# DM3390_TopLevel.net
KiCad netlist of a schematic drawn in Altium Designer
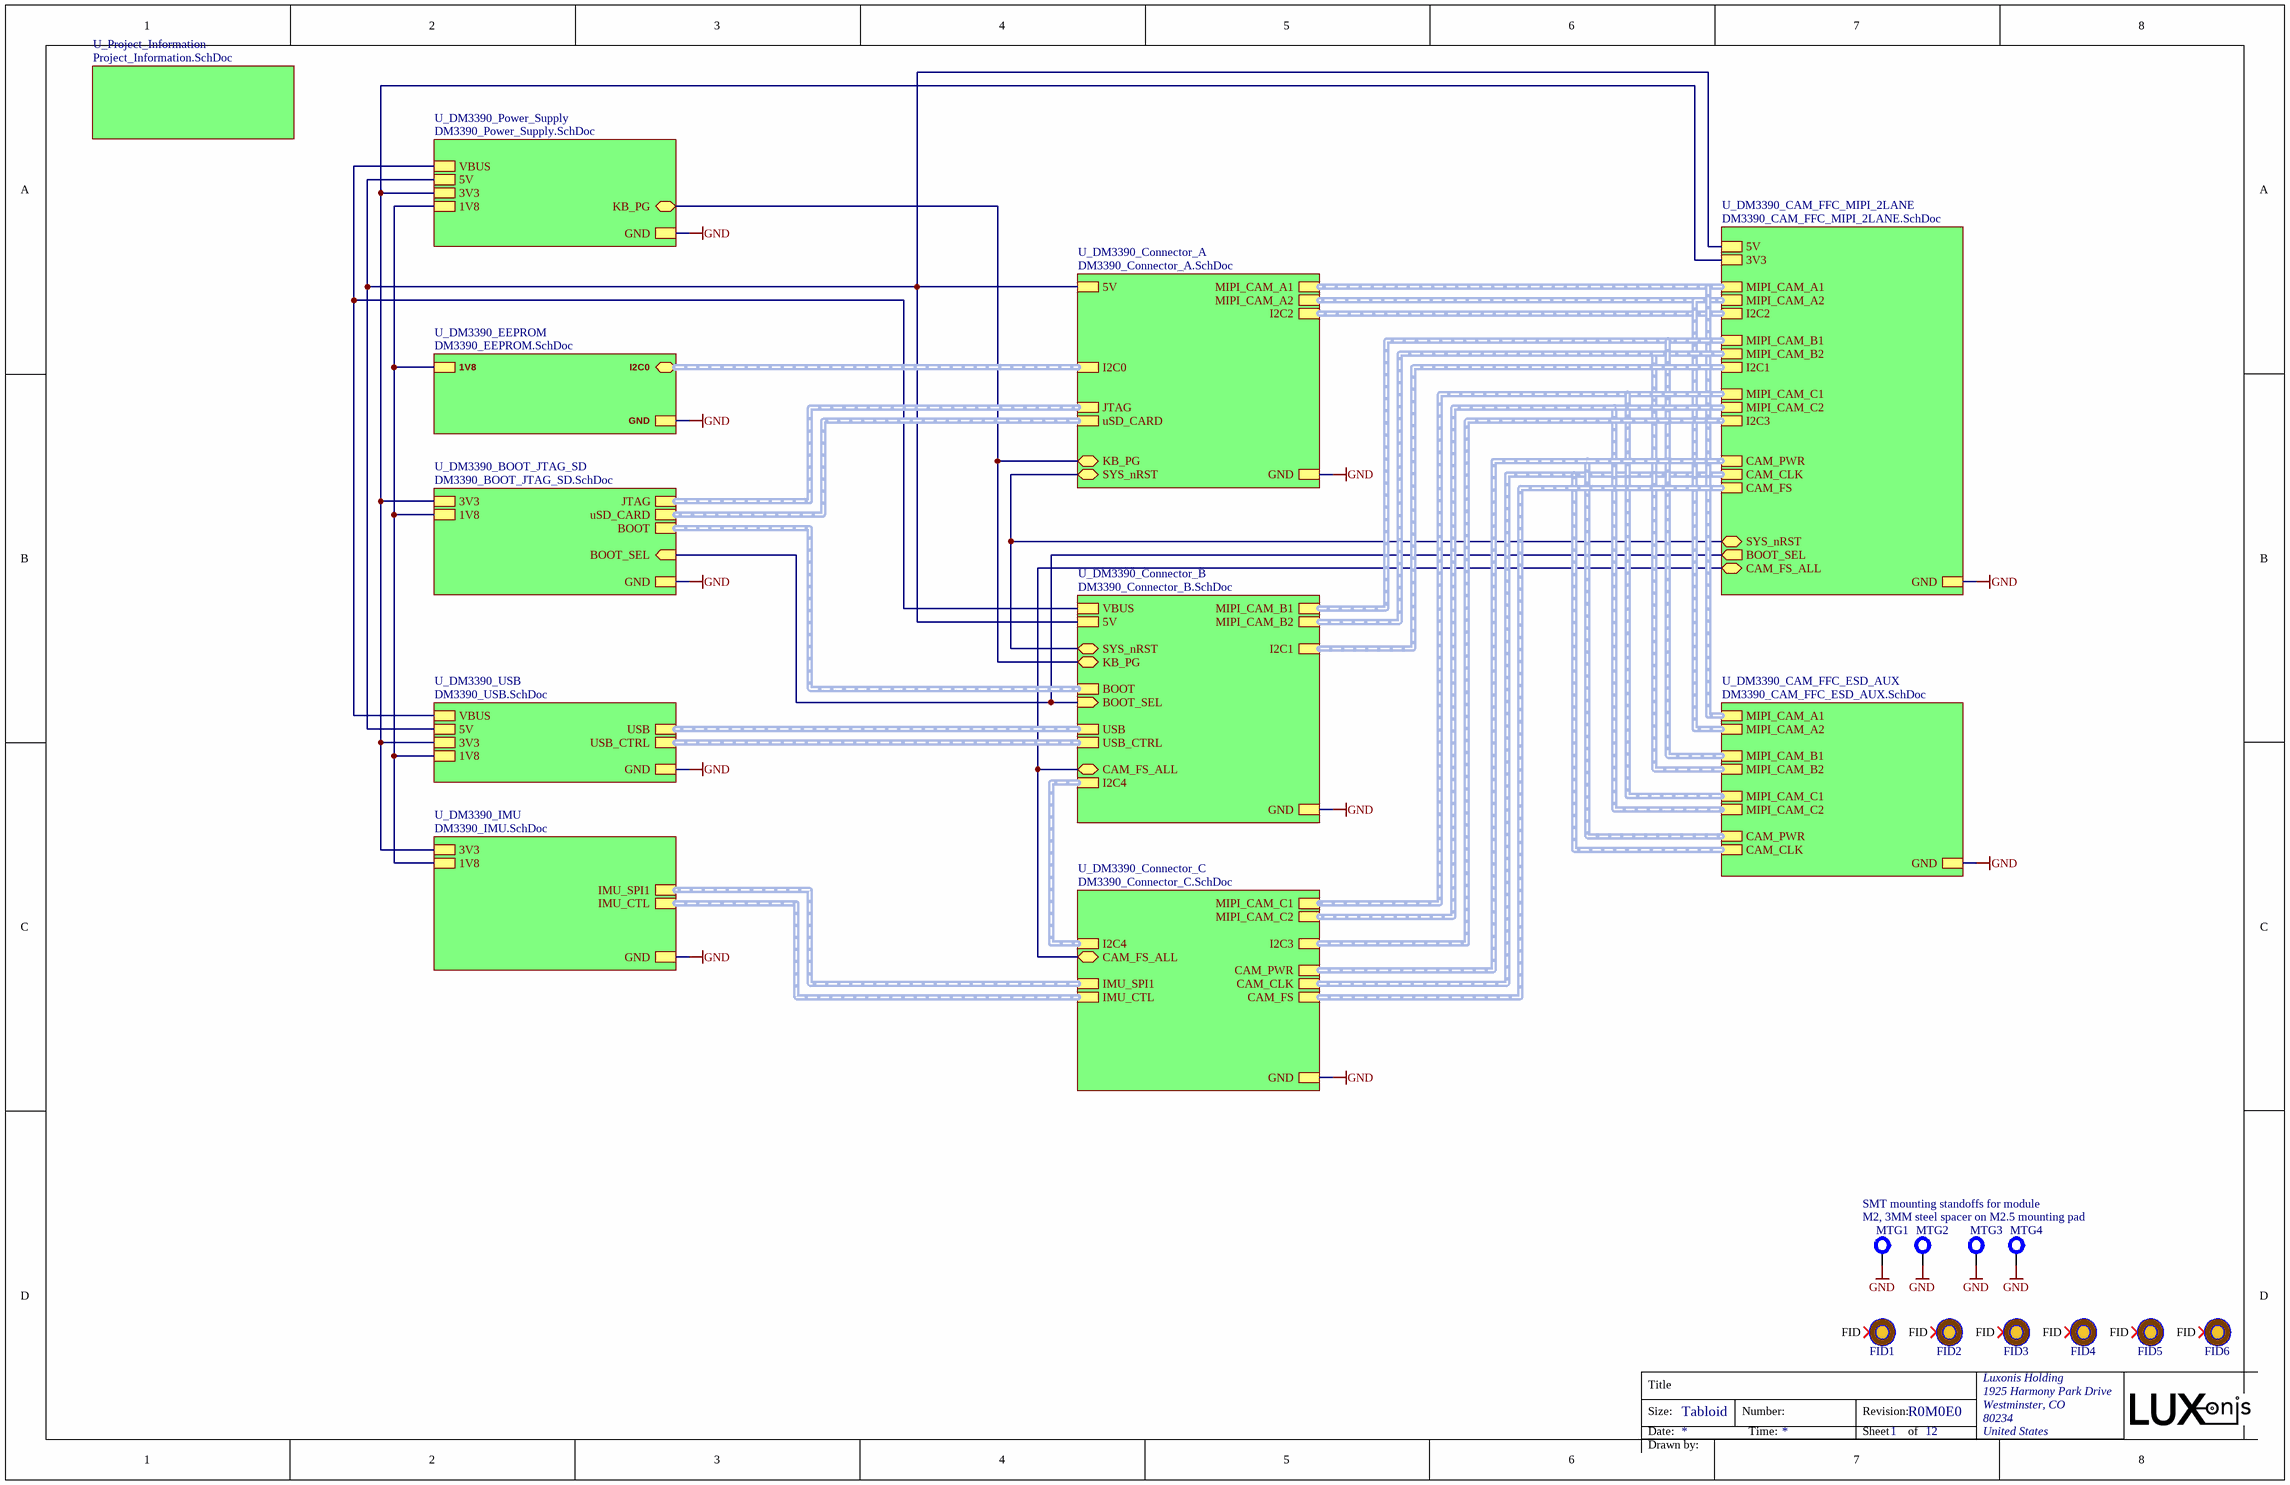
[diagram p0: DM3390_TopLevel.SchDoc]

(export (version "E")
  (design (tool "Eeschema 10.0.6"))
  (components
    (comp (ref "FID1")
      (value "FIDUCIAL_ROUND_1MM")
      (footprint "LuxonisMaster:FIDUCIAL_ROUND_1MM")
      (description "Fiducial with various available footprints")
      (libsource (lib "LuxonisMaster") (part "FIDUCIAL"))
    )
    (comp (ref "FID2")
      (value "FIDUCIAL_ROUND_1MM")
      (footprint "LuxonisMaster:FIDUCIAL_ROUND_1MM")
      (description "Fiducial with various available footprints")
      (libsource (lib "LuxonisMaster") (part "FIDUCIAL"))
    )
    (comp (ref "FID3")
      (value "FIDUCIAL_ROUND_1MM")
      (footprint "LuxonisMaster:FIDUCIAL_ROUND_1MM")
      (description "Fiducial with various available footprints")
      (libsource (lib "LuxonisMaster") (part "FIDUCIAL"))
    )
    (comp (ref "FID4")
      (value "FIDUCIAL_ROUND_1MM")
      (footprint "LuxonisMaster:FIDUCIAL_ROUND_1MM")
      (description "Fiducial with various available footprints")
      (libsource (lib "LuxonisMaster") (part "FIDUCIAL"))
    )
    (comp (ref "FID5")
      (value "FIDUCIAL_ROUND_1MM")
      (footprint "LuxonisMaster:FIDUCIAL_ROUND_1MM")
      (description "Fiducial with various available footprints")
      (libsource (lib "LuxonisMaster") (part "FIDUCIAL"))
    )
    (comp (ref "FID6")
      (value "FIDUCIAL_ROUND_1MM")
      (footprint "LuxonisMaster:FIDUCIAL_ROUND_1MM")
      (description "Fiducial with various available footprints")
      (libsource (lib "LuxonisMaster") (part "FIDUCIAL"))
    )
    (comp (ref "MTG1")
      (value "M2, 3MM steel spacer on M2.5 mounting pad")
      (footprint "LuxonisMaster:9774030243R")
      (description "MP ROUND STANDOFF M2X0.4 STEEL 3MM")
      (libsource (lib "LuxonisMaster") (part "9774030243R"))
    )
    (comp (ref "MTG2")
      (value "M2, 3MM steel spacer on M2.5 mounting pad")
      (footprint "LuxonisMaster:9774030243R")
      (description "MP ROUND STANDOFF M2X0.4 STEEL 3MM")
      (libsource (lib "LuxonisMaster") (part "9774030243R"))
    )
    (comp (ref "MTG3")
      (value "M2, 3MM steel spacer on M2.5 mounting pad")
      (footprint "LuxonisMaster:9774030243R")
      (description "MP ROUND STANDOFF M2X0.4 STEEL 3MM")
      (libsource (lib "LuxonisMaster") (part "9774030243R"))
    )
    (comp (ref "MTG4")
      (value "M2, 3MM steel spacer on M2.5 mounting pad")
      (footprint "LuxonisMaster:9774030243R")
      (description "MP ROUND STANDOFF M2X0.4 STEEL 3MM")
      (libsource (lib "LuxonisMaster") (part "9774030243R"))
    )
  )
  (nets
    (net (code "30") (name "GND") (class "Default")
      (node (ref "MTG1") (pin "1") (pintype "passive"))
      (node (ref "MTG2") (pin "1") (pintype "passive"))
      (node (ref "MTG3") (pin "1") (pintype "passive"))
      (node (ref "MTG4") (pin "1") (pintype "passive"))
    )
    (net (code "31") (name "unconnected-(FID1-PadFID)") (class "Default")
      (node (ref "FID1") (pin "FID") (pinfunction "FID_FID") (pintype "input+no_connect"))
    )
    (net (code "32") (name "unconnected-(FID2-PadFID)") (class "Default")
      (node (ref "FID2") (pin "FID") (pinfunction "FID_FID") (pintype "input+no_connect"))
    )
    (net (code "33") (name "unconnected-(FID3-PadFID)") (class "Default")
      (node (ref "FID3") (pin "FID") (pinfunction "FID_FID") (pintype "input+no_connect"))
    )
    (net (code "34") (name "unconnected-(FID4-PadFID)") (class "Default")
      (node (ref "FID4") (pin "FID") (pinfunction "FID_FID") (pintype "input+no_connect"))
    )
    (net (code "35") (name "unconnected-(FID5-PadFID)") (class "Default")
      (node (ref "FID5") (pin "FID") (pinfunction "FID_FID") (pintype "input+no_connect"))
    )
    (net (code "36") (name "unconnected-(FID6-PadFID)") (class "Default")
      (node (ref "FID6") (pin "FID") (pinfunction "FID_FID") (pintype "input+no_connect"))
    )
  )
)
